# shinobi.net
KiCad netlist of a schematic drawn in EAGLE
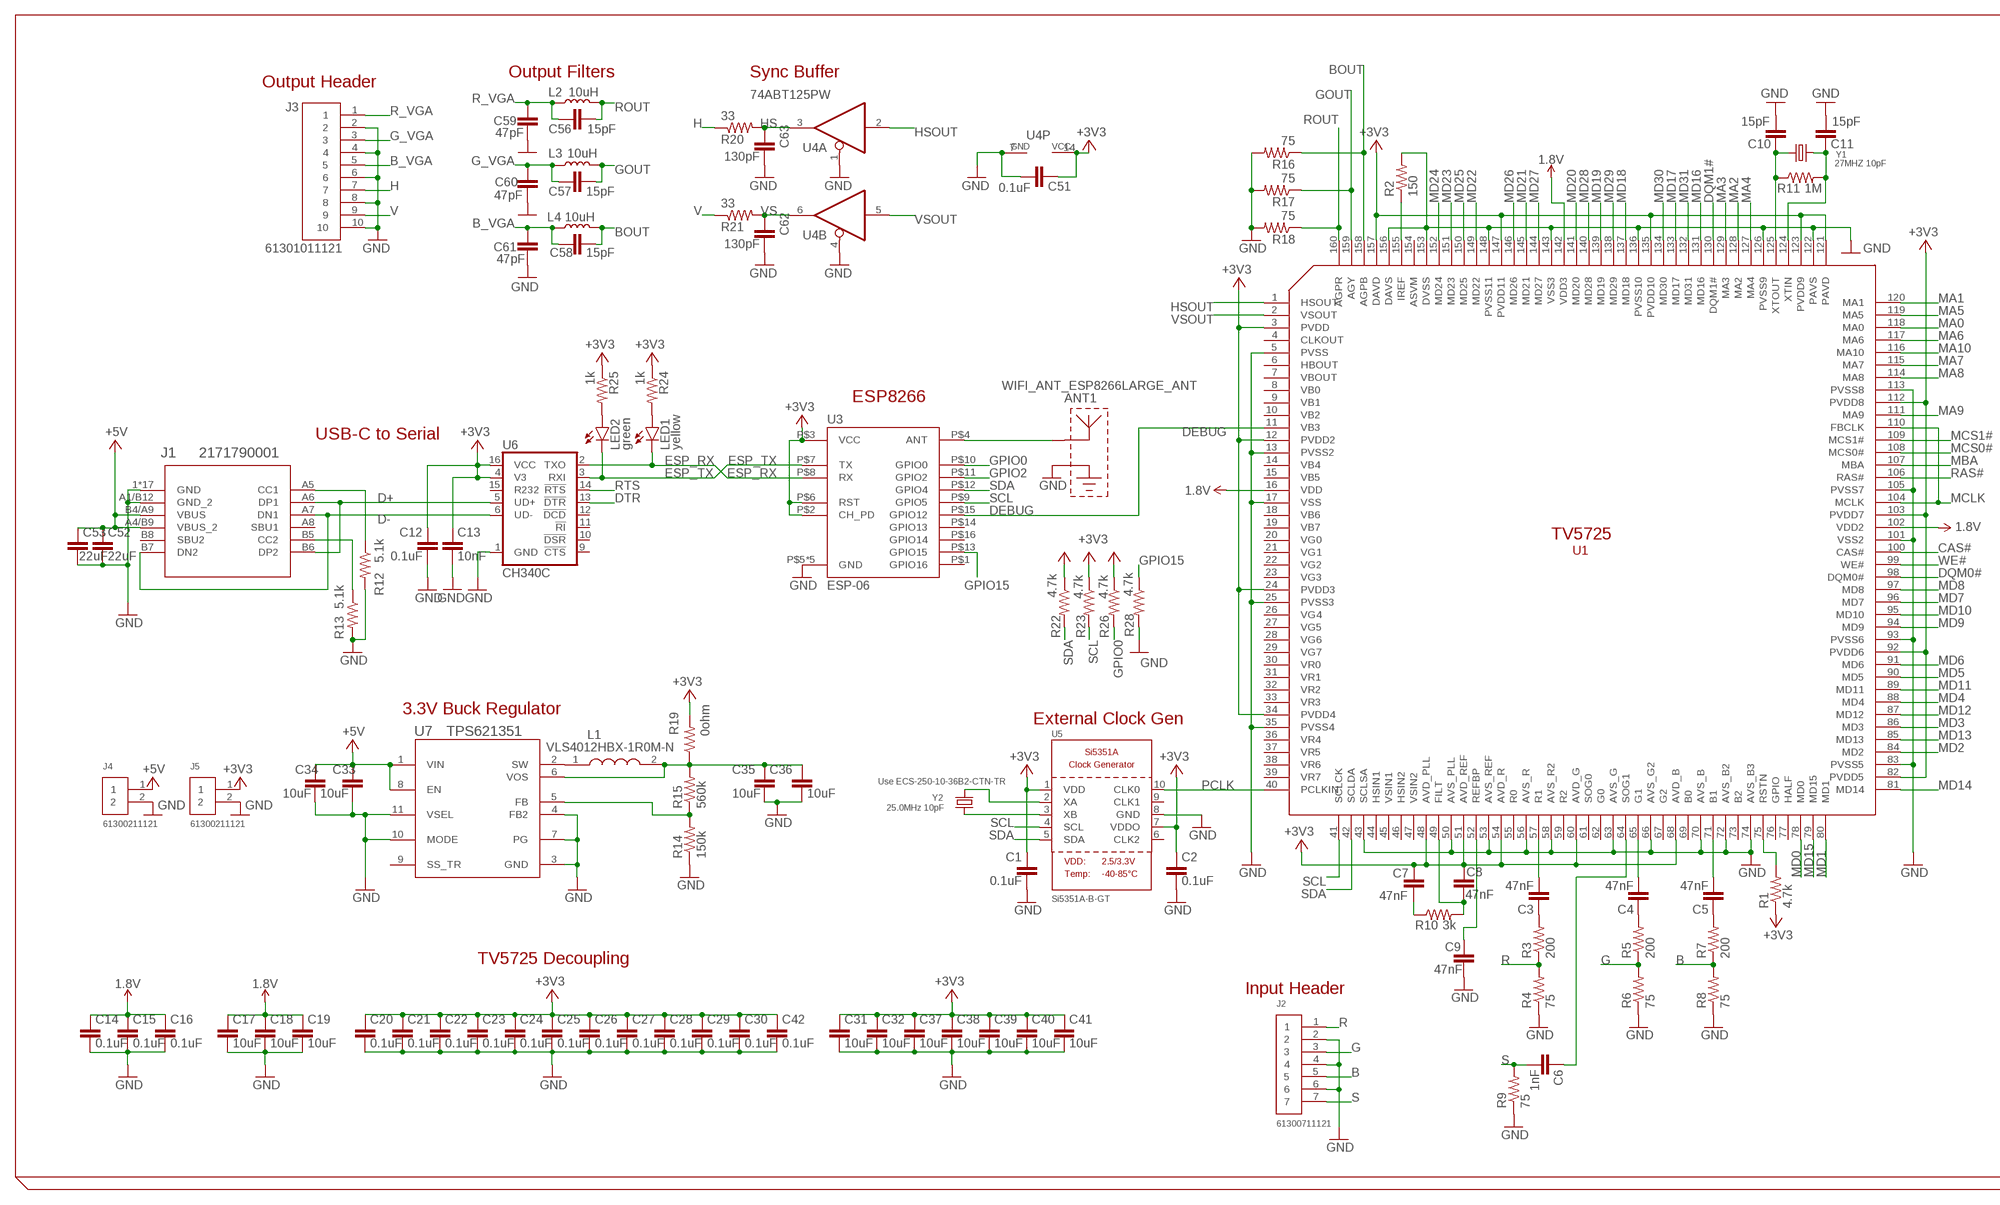
[diagram p0: schematic, sheet 1, part 1 of 2]
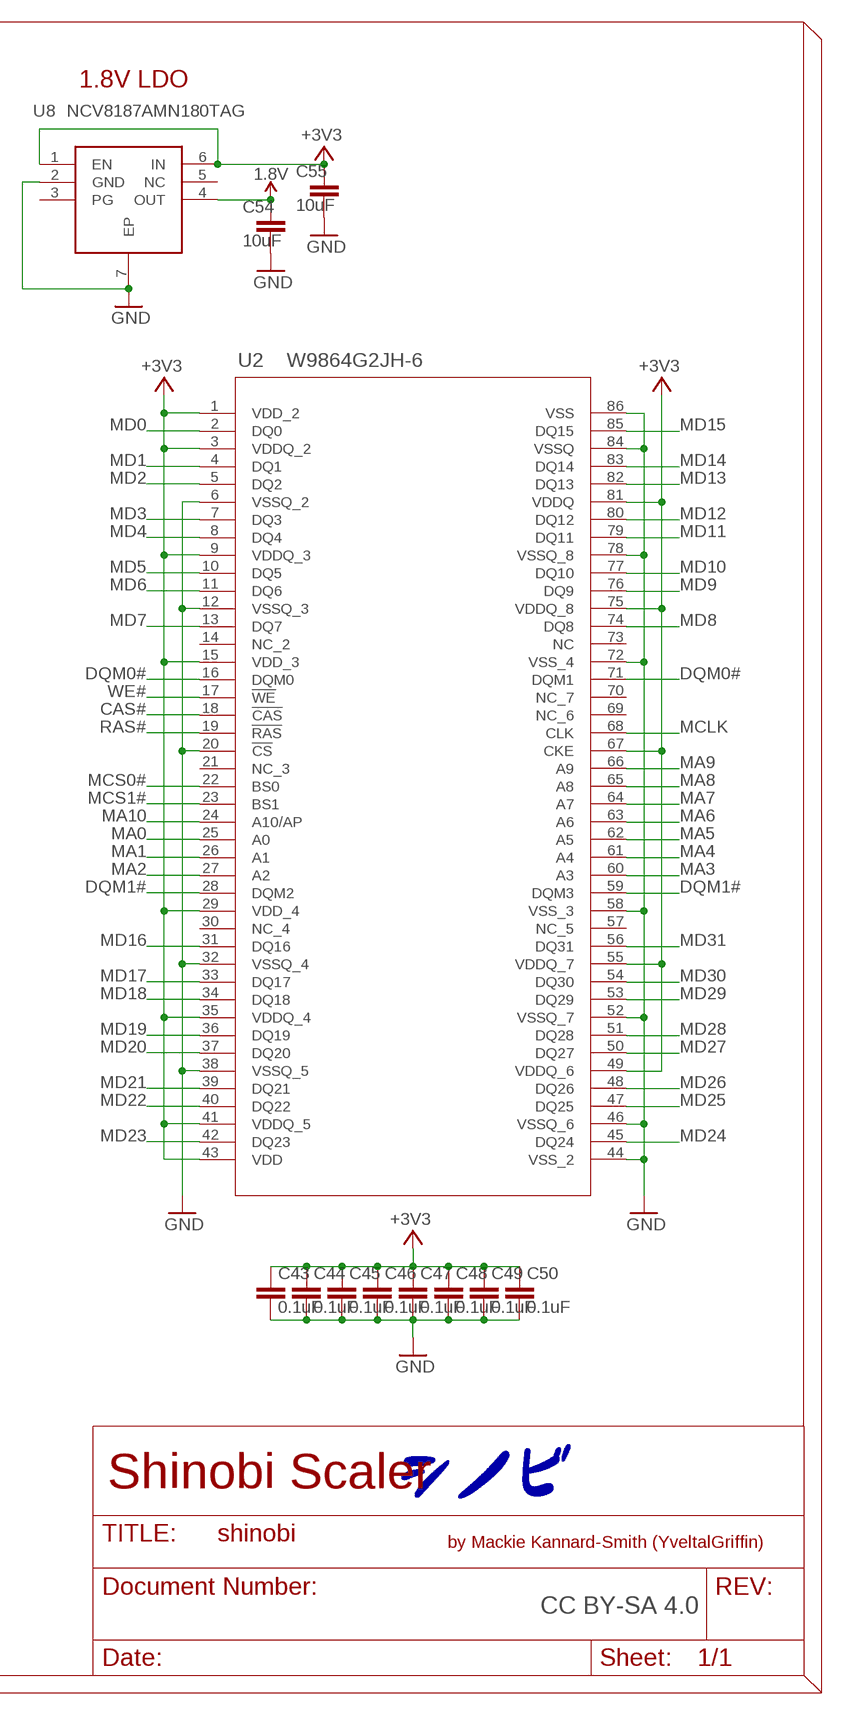
[diagram p1: schematic, sheet 1, part 2 of 2]

(export (version "E")
  (design (tool "Eeschema 10.0.6"))
  (components
    (comp (ref "ANT1")
      (value "WIFI_ANT_ESP8266LARGE_ANT")
      (footprint "eagle-import:ANTENNA")
      (libsource (lib "eagle-import") (part "WIFI_ANT_ESP8266LARGE_ANT"))
    )
    (comp (ref "C1")
      (value "0.1uF")
      (footprint "eagle-import:C0402")
      (libsource (lib "eagle-import") (part "C-USC0402"))
    )
    (comp (ref "C2")
      (value "0.1uF")
      (footprint "eagle-import:C0402")
      (libsource (lib "eagle-import") (part "C-USC0402"))
    )
    (comp (ref "C3")
      (value "47nF")
      (footprint "eagle-import:C0402")
      (libsource (lib "eagle-import") (part "C-USC0402"))
    )
    (comp (ref "C4")
      (value "47nF")
      (footprint "eagle-import:C0402")
      (libsource (lib "eagle-import") (part "C-USC0402"))
    )
    (comp (ref "C5")
      (value "47nF")
      (footprint "eagle-import:C0402")
      (libsource (lib "eagle-import") (part "C-USC0402"))
    )
    (comp (ref "C6")
      (value "1nF")
      (footprint "eagle-import:C0402")
      (libsource (lib "eagle-import") (part "C-USC0402"))
    )
    (comp (ref "C7")
      (value "47nF")
      (footprint "eagle-import:C0402")
      (libsource (lib "eagle-import") (part "C-USC0402"))
    )
    (comp (ref "C8")
      (value "47nF")
      (footprint "eagle-import:C0402")
      (libsource (lib "eagle-import") (part "C-USC0402"))
    )
    (comp (ref "C9")
      (value "47nF")
      (footprint "eagle-import:C0402")
      (libsource (lib "eagle-import") (part "C-USC0402"))
    )
    (comp (ref "C10")
      (value "15pF")
      (footprint "eagle-import:C0402")
      (libsource (lib "eagle-import") (part "C-USC0402"))
    )
    (comp (ref "C11")
      (value "15pF")
      (footprint "eagle-import:C0402")
      (libsource (lib "eagle-import") (part "C-USC0402"))
    )
    (comp (ref "C12")
      (value "0.1uF")
      (footprint "eagle-import:C0402")
      (libsource (lib "eagle-import") (part "C-USC0402"))
    )
    (comp (ref "C13")
      (value "10nF")
      (footprint "eagle-import:C0402")
      (libsource (lib "eagle-import") (part "C-USC0402"))
    )
    (comp (ref "C14")
      (value "0.1uF")
      (footprint "eagle-import:C0402")
      (libsource (lib "eagle-import") (part "C-USC0402"))
    )
    (comp (ref "C15")
      (value "0.1uF")
      (footprint "eagle-import:C0402")
      (libsource (lib "eagle-import") (part "C-USC0402"))
    )
    (comp (ref "C16")
      (value "0.1uF")
      (footprint "eagle-import:C0402")
      (libsource (lib "eagle-import") (part "C-USC0402"))
    )
    (comp (ref "C17")
      (value "10uF")
      (footprint "eagle-import:C0603")
      (libsource (lib "eagle-import") (part "C-USC0603"))
    )
    (comp (ref "C18")
      (value "10uF")
      (footprint "eagle-import:C0603")
      (libsource (lib "eagle-import") (part "C-USC0603"))
    )
    (comp (ref "C19")
      (value "10uF")
      (footprint "eagle-import:C0603")
      (libsource (lib "eagle-import") (part "C-USC0603"))
    )
    (comp (ref "C20")
      (value "0.1uF")
      (footprint "eagle-import:C0402")
      (libsource (lib "eagle-import") (part "C-USC0402"))
    )
    (comp (ref "C21")
      (value "0.1uF")
      (footprint "eagle-import:C0402")
      (libsource (lib "eagle-import") (part "C-USC0402"))
    )
    (comp (ref "C22")
      (value "0.1uF")
      (footprint "eagle-import:C0402")
      (libsource (lib "eagle-import") (part "C-USC0402"))
    )
    (comp (ref "C23")
      (value "0.1uF")
      (footprint "eagle-import:C0402")
      (libsource (lib "eagle-import") (part "C-USC0402"))
    )
    (comp (ref "C24")
      (value "0.1uF")
      (footprint "eagle-import:C0402")
      (libsource (lib "eagle-import") (part "C-USC0402"))
    )
    (comp (ref "C25")
      (value "0.1uF")
      (footprint "eagle-import:C0402")
      (libsource (lib "eagle-import") (part "C-USC0402"))
    )
    (comp (ref "C26")
      (value "0.1uF")
      (footprint "eagle-import:C0402")
      (libsource (lib "eagle-import") (part "C-USC0402"))
    )
    (comp (ref "C27")
      (value "0.1uF")
      (footprint "eagle-import:C0402")
      (libsource (lib "eagle-import") (part "C-USC0402"))
    )
    (comp (ref "C28")
      (value "0.1uF")
      (footprint "eagle-import:C0402")
      (libsource (lib "eagle-import") (part "C-USC0402"))
    )
    (comp (ref "C29")
      (value "0.1uF")
      (footprint "eagle-import:C0402")
      (libsource (lib "eagle-import") (part "C-USC0402"))
    )
    (comp (ref "C30")
      (value "0.1uF")
      (footprint "eagle-import:C0402")
      (libsource (lib "eagle-import") (part "C-USC0402"))
    )
    (comp (ref "C31")
      (value "10uF")
      (footprint "eagle-import:C0603")
      (libsource (lib "eagle-import") (part "C-USC0603"))
    )
    (comp (ref "C32")
      (value "10uF")
      (footprint "eagle-import:C0603")
      (libsource (lib "eagle-import") (part "C-USC0603"))
    )
    (comp (ref "C33")
      (value "10uF")
      (footprint "eagle-import:C0603")
      (libsource (lib "eagle-import") (part "C-USC0603"))
    )
    (comp (ref "C34")
      (value "10uF")
      (footprint "eagle-import:C0603")
      (libsource (lib "eagle-import") (part "C-USC0603"))
    )
    (comp (ref "C35")
      (value "10uF")
      (footprint "eagle-import:C0603")
      (libsource (lib "eagle-import") (part "C-USC0603"))
    )
    (comp (ref "C36")
      (value "10uF")
      (footprint "eagle-import:C0603")
      (libsource (lib "eagle-import") (part "C-USC0603"))
    )
    (comp (ref "C37")
      (value "10uF")
      (footprint "eagle-import:C0603")
      (libsource (lib "eagle-import") (part "C-USC0603"))
    )
    (comp (ref "C38")
      (value "10uF")
      (footprint "eagle-import:C0603")
      (libsource (lib "eagle-import") (part "C-USC0603"))
    )
    (comp (ref "C39")
      (value "10uF")
      (footprint "eagle-import:C0603")
      (libsource (lib "eagle-import") (part "C-USC0603"))
    )
    (comp (ref "C40")
      (value "10uF")
      (footprint "eagle-import:C0603")
      (libsource (lib "eagle-import") (part "C-USC0603"))
    )
    (comp (ref "C41")
      (value "10uF")
      (footprint "eagle-import:C0603")
      (libsource (lib "eagle-import") (part "C-USC0603"))
    )
    (comp (ref "C42")
      (value "0.1uF")
      (footprint "eagle-import:C0402")
      (libsource (lib "eagle-import") (part "C-USC0402"))
    )
    (comp (ref "C43")
      (value "0.1uF")
      (footprint "eagle-import:C0402")
      (libsource (lib "eagle-import") (part "C-USC0402"))
    )
    (comp (ref "C44")
      (value "0.1uF")
      (footprint "eagle-import:C0402")
      (libsource (lib "eagle-import") (part "C-USC0402"))
    )
    (comp (ref "C45")
      (value "0.1uF")
      (footprint "eagle-import:C0402")
      (libsource (lib "eagle-import") (part "C-USC0402"))
    )
    (comp (ref "C46")
      (value "0.1uF")
      (footprint "eagle-import:C0402")
      (libsource (lib "eagle-import") (part "C-USC0402"))
    )
    (comp (ref "C47")
      (value "0.1uF")
      (footprint "eagle-import:C0402")
      (libsource (lib "eagle-import") (part "C-USC0402"))
    )
    (comp (ref "C48")
      (value "0.1uF")
      (footprint "eagle-import:C0402")
      (libsource (lib "eagle-import") (part "C-USC0402"))
    )
    (comp (ref "C49")
      (value "0.1uF")
      (footprint "eagle-import:C0402")
      (libsource (lib "eagle-import") (part "C-USC0402"))
    )
    (comp (ref "C50")
      (value "0.1uF")
      (footprint "eagle-import:C0402")
      (libsource (lib "eagle-import") (part "C-USC0402"))
    )
    (comp (ref "C51")
      (value "0.1uF")
      (footprint "eagle-import:C0402")
      (libsource (lib "eagle-import") (part "C-USC0402"))
    )
    (comp (ref "C52")
      (value "22uF")
      (footprint "eagle-import:C0805")
      (libsource (lib "eagle-import") (part "C-USC0805"))
    )
    (comp (ref "C53")
      (value "22uF")
      (footprint "eagle-import:C0805")
      (libsource (lib "eagle-import") (part "C-USC0805"))
    )
    (comp (ref "C54")
      (value "10uF")
      (footprint "eagle-import:C0603")
      (libsource (lib "eagle-import") (part "C-USC0603"))
    )
    (comp (ref "C55")
      (value "10uF")
      (footprint "eagle-import:C0603")
      (libsource (lib "eagle-import") (part "C-USC0603"))
    )
    (comp (ref "C56")
      (value "15pF")
      (footprint "eagle-import:C0402")
      (libsource (lib "eagle-import") (part "C-USC0402"))
    )
    (comp (ref "C57")
      (value "15pF")
      (footprint "eagle-import:C0402")
      (libsource (lib "eagle-import") (part "C-USC0402"))
    )
    (comp (ref "C58")
      (value "15pF")
      (footprint "eagle-import:C0402")
      (libsource (lib "eagle-import") (part "C-USC0402"))
    )
    (comp (ref "C59")
      (value "47pF")
      (footprint "eagle-import:C0402")
      (libsource (lib "eagle-import") (part "C-USC0402"))
    )
    (comp (ref "C60")
      (value "47pF")
      (footprint "eagle-import:C0402")
      (libsource (lib "eagle-import") (part "C-USC0402"))
    )
    (comp (ref "C61")
      (value "47pF")
      (footprint "eagle-import:C0402")
      (libsource (lib "eagle-import") (part "C-USC0402"))
    )
    (comp (ref "C62")
      (value "130pF")
      (footprint "eagle-import:C0402")
      (libsource (lib "eagle-import") (part "C-USC0402"))
    )
    (comp (ref "C63")
      (value "130pF")
      (footprint "eagle-import:C0402")
      (libsource (lib "eagle-import") (part "C-USC0402"))
    )
    (comp (ref "J1")
      (value "2171790001")
      (footprint "eagle-import:2171790001_MOL")
      (fields (field (name "COPYRIGHT") "Copyright (C) 2022 Ultra Librarian. All rights reserved."))
      (libsource (lib "eagle-import") (part "2171790001"))
    )
    (comp (ref "J2")
      (value "61300711121")
      (footprint "eagle-import:61300711121")
      (fields
        (field (name "DIGI_KEY_PART_NUMBER") "732-5320-ND")
        (field (name "MANUFACTURER") "Wurth Electronics Inc.")
        (field (name "CREATED_BY") "PCBLayout.com")
      )
      (libsource (lib "eagle-import") (part "61300711121"))
    )
    (comp (ref "J3")
      (value "61301011121")
      (footprint "eagle-import:61301011121")
      (fields
        (field (name "DIGIKEY_PART_NUMBER") "732-2670-ND")
        (field (name "MANUFACTURER") "Wurth Electronics Inc.")
        (field (name "CREATED_BY") "PCBLayout.com")
      )
      (libsource (lib "eagle-import") (part "61301011121"))
    )
    (comp (ref "J4")
      (value "61300211121")
      (footprint "eagle-import:61300211121")
      (fields
        (field (name "DIGI_KEY_PART_NUMBER") "732-5315-ND")
        (field (name "MANUFACTURER") "Wurth Electronics Inc.")
        (field (name "CREATED_BY") "PCBLayout.com")
      )
      (libsource (lib "eagle-import") (part "61300211121"))
    )
    (comp (ref "J5")
      (value "61300211121")
      (footprint "eagle-import:61300211121")
      (fields
        (field (name "DIGI_KEY_PART_NUMBER") "732-5315-ND")
        (field (name "MANUFACTURER") "Wurth Electronics Inc.")
        (field (name "CREATED_BY") "PCBLayout.com")
      )
      (libsource (lib "eagle-import") (part "61300211121"))
    )
    (comp (ref "L1")
      (value "VLS4012HBX-1R0M-N")
      (footprint "eagle-import:VLS4012")
      (fields (field (name "MOUSER_PART_NUMBER") "810-VLS4012HBX1R0M-N"))
      (libsource (lib "eagle-import") (part "VLS4012HBX-1R0M-N"))
    )
    (comp (ref "L2")
      (value "10uH")
      (footprint "eagle-import:R0402")
      (libsource (lib "eagle-import") (part "L0402"))
    )
    (comp (ref "L3")
      (value "10uH")
      (footprint "eagle-import:R0402")
      (libsource (lib "eagle-import") (part "L0402"))
    )
    (comp (ref "L4")
      (value "10uH")
      (footprint "eagle-import:R0402")
      (libsource (lib "eagle-import") (part "L0402"))
    )
    (comp (ref "LED1")
      (value "yellow")
      (footprint "eagle-import:CHIP-LED0603")
      (libsource (lib "eagle-import") (part "LEDCHIP-LED0603"))
    )
    (comp (ref "LED2")
      (value "green")
      (footprint "eagle-import:CHIP-LED0603")
      (libsource (lib "eagle-import") (part "LEDCHIP-LED0603"))
    )
    (comp (ref "R1")
      (value "4.7k")
      (footprint "eagle-import:R0402")
      (libsource (lib "eagle-import") (part "R-US_R0402"))
    )
    (comp (ref "R2")
      (value "150")
      (footprint "eagle-import:R0402")
      (libsource (lib "eagle-import") (part "R-US_R0402"))
    )
    (comp (ref "R3")
      (value "200")
      (footprint "eagle-import:R0402")
      (libsource (lib "eagle-import") (part "R-US_R0402"))
    )
    (comp (ref "R4")
      (value "75")
      (footprint "eagle-import:R0402")
      (libsource (lib "eagle-import") (part "R-US_R0402"))
    )
    (comp (ref "R5")
      (value "200")
      (footprint "eagle-import:R0402")
      (libsource (lib "eagle-import") (part "R-US_R0402"))
    )
    (comp (ref "R6")
      (value "75")
      (footprint "eagle-import:R0402")
      (libsource (lib "eagle-import") (part "R-US_R0402"))
    )
    (comp (ref "R7")
      (value "200")
      (footprint "eagle-import:R0402")
      (libsource (lib "eagle-import") (part "R-US_R0402"))
    )
    (comp (ref "R8")
      (value "75")
      (footprint "eagle-import:R0402")
      (libsource (lib "eagle-import") (part "R-US_R0402"))
    )
    (comp (ref "R9")
      (value "75")
      (footprint "eagle-import:R0402")
      (libsource (lib "eagle-import") (part "R-US_R0402"))
    )
    (comp (ref "R10")
      (value "3k")
      (footprint "eagle-import:R0402")
      (libsource (lib "eagle-import") (part "R-US_R0402"))
    )
    (comp (ref "R11")
      (value "1M")
      (footprint "eagle-import:R0402")
      (libsource (lib "eagle-import") (part "R-US_R0402"))
    )
    (comp (ref "R12")
      (value "5.1k")
      (footprint "eagle-import:R0402")
      (libsource (lib "eagle-import") (part "R-US_R0402"))
    )
    (comp (ref "R13")
      (value "5.1k")
      (footprint "eagle-import:R0402")
      (libsource (lib "eagle-import") (part "R-US_R0402"))
    )
    (comp (ref "R14")
      (value "150k")
      (footprint "eagle-import:R0402")
      (libsource (lib "eagle-import") (part "R-US_R0402"))
    )
    (comp (ref "R15")
      (value "560k")
      (footprint "eagle-import:R0402")
      (libsource (lib "eagle-import") (part "R-US_R0402"))
    )
    (comp (ref "R16")
      (value "75")
      (footprint "eagle-import:R0402")
      (libsource (lib "eagle-import") (part "R-US_R0402"))
    )
    (comp (ref "R17")
      (value "75")
      (footprint "eagle-import:R0402")
      (libsource (lib "eagle-import") (part "R-US_R0402"))
    )
    (comp (ref "R18")
      (value "75")
      (footprint "eagle-import:R0402")
      (libsource (lib "eagle-import") (part "R-US_R0402"))
    )
    (comp (ref "R19")
      (value "0ohm")
      (footprint "eagle-import:R0805")
      (libsource (lib "eagle-import") (part "R-US_R0805"))
    )
    (comp (ref "R20")
      (value "33")
      (footprint "eagle-import:R0402")
      (libsource (lib "eagle-import") (part "R-US_R0402"))
    )
    (comp (ref "R21")
      (value "33")
      (footprint "eagle-import:R0402")
      (libsource (lib "eagle-import") (part "R-US_R0402"))
    )
    (comp (ref "R22")
      (value "4.7k")
      (footprint "eagle-import:R0402")
      (libsource (lib "eagle-import") (part "R-US_R0402"))
    )
    (comp (ref "R23")
      (value "4.7k")
      (footprint "eagle-import:R0402")
      (libsource (lib "eagle-import") (part "R-US_R0402"))
    )
    (comp (ref "R24")
      (value "1k")
      (footprint "eagle-import:R0402")
      (libsource (lib "eagle-import") (part "R-US_R0402"))
    )
    (comp (ref "R25")
      (value "1k")
      (footprint "eagle-import:R0402")
      (libsource (lib "eagle-import") (part "R-US_R0402"))
    )
    (comp (ref "R26")
      (value "4.7k")
      (footprint "eagle-import:R0402")
      (libsource (lib "eagle-import") (part "R-US_R0402"))
    )
    (comp (ref "R28")
      (value "4.7k")
      (footprint "eagle-import:R0402")
      (libsource (lib "eagle-import") (part "R-US_R0402"))
    )
    (comp (ref "U1")
      (value "TV5725")
      (footprint "eagle-import:PQFP160")
      (libsource (lib "eagle-import") (part "TV5725"))
    )
    (comp (ref "U2")
      (value "W9864G2JH-6")
      (footprint "eagle-import:WIN_TSOP-86_WIN")
      (fields (field (name "COPYRIGHT") "Copyright (C) 2022 Ultra Librarian. All rights reserved."))
      (libsource (lib "eagle-import") (part "W9864G2JH-6"))
    )
    (comp (ref "U3")
      (value "ESP-06")
      (footprint "eagle-import:ESP-06")
      (libsource (lib "eagle-import") (part "ESP-06"))
    )
    (comp (ref "U4")
      (value "74ABT125PW")
      (footprint "eagle-import:TSSOP14")
      (libsource (lib "eagle-import") (part "74125PWABT"))
    )
    (comp (ref "U5")
      (value "Si5351A-B-GT")
      (footprint "eagle-import:MSOP10")
      (libsource (lib "eagle-import") (part "SI5351A"))
    )
    (comp (ref "U6")
      (value "CH340C")
      (footprint "eagle-import:SO016")
      (libsource (lib "eagle-import") (part "CH340C"))
    )
    (comp (ref "U7")
      (value "TPS621351")
      (footprint "eagle-import:RGX0011A")
      (fields
        (field (name "MANUFACTURER") "Texas Instruments")
        (field (name "MANUFACTURER_PART_NUMBER") "TPS621351RGXR")
      )
      (libsource (lib "eagle-import") (part "TPS621351RGXR"))
    )
    (comp (ref "U8")
      (value "NCV8187AMN180TAG")
      (footprint "eagle-import:SON95P300X300X95-7N")
      (fields (field (name "MOUSER_PART_NUMBER") "863-NCV8187AMN180TAG"))
      (libsource (lib "eagle-import") (part "NCV8187AMN180TAG"))
    )
    (comp (ref "Y1")
      (value "27MHZ 10pF")
      (footprint "eagle-import:CRYSTAL_2.5X2")
      (libsource (lib "eagle-import") (part "CRYSTAL2.5X2.0"))
    )
    (comp (ref "Y2")
      (value "25.0MHz 10pF")
      (footprint "eagle-import:CRYSTAL_2.5X2")
      (libsource (lib "eagle-import") (part "CRYSTAL2.5X2.0"))
    )
  )
  (nets
    (net (code "1") (name "+3V3") (class "Default")
      (node (ref "C1") (pin "1") (pinfunction "1_1") (pintype "passive"))
      (node (ref "C12") (pin "1") (pinfunction "1_1") (pintype "passive"))
      (node (ref "C13") (pin "1") (pinfunction "1_1") (pintype "passive"))
      (node (ref "C2") (pin "1") (pinfunction "1_1") (pintype "passive"))
      (node (ref "C20") (pin "1") (pinfunction "1_1") (pintype "passive"))
      (node (ref "C21") (pin "1") (pinfunction "1_1") (pintype "passive"))
      (node (ref "C22") (pin "1") (pinfunction "1_1") (pintype "passive"))
      (node (ref "C23") (pin "1") (pinfunction "1_1") (pintype "passive"))
      (node (ref "C24") (pin "1") (pinfunction "1_1") (pintype "passive"))
      (node (ref "C25") (pin "1") (pinfunction "1_1") (pintype "passive"))
      (node (ref "C26") (pin "1") (pinfunction "1_1") (pintype "passive"))
      (node (ref "C27") (pin "1") (pinfunction "1_1") (pintype "passive"))
      (node (ref "C28") (pin "1") (pinfunction "1_1") (pintype "passive"))
      (node (ref "C29") (pin "1") (pinfunction "1_1") (pintype "passive"))
      (node (ref "C30") (pin "1") (pinfunction "1_1") (pintype "passive"))
      (node (ref "C31") (pin "1") (pinfunction "1_1") (pintype "passive"))
      (node (ref "C32") (pin "1") (pinfunction "1_1") (pintype "passive"))
      (node (ref "C37") (pin "1") (pinfunction "1_1") (pintype "passive"))
      (node (ref "C38") (pin "1") (pinfunction "1_1") (pintype "passive"))
      (node (ref "C39") (pin "1") (pinfunction "1_1") (pintype "passive"))
      (node (ref "C40") (pin "1") (pinfunction "1_1") (pintype "passive"))
      (node (ref "C41") (pin "1") (pinfunction "1_1") (pintype "passive"))
      (node (ref "C42") (pin "1") (pinfunction "1_1") (pintype "passive"))
      (node (ref "C43") (pin "1") (pinfunction "1_1") (pintype "passive"))
      (node (ref "C44") (pin "1") (pinfunction "1_1") (pintype "passive"))
      (node (ref "C45") (pin "1") (pinfunction "1_1") (pintype "passive"))
      (node (ref "C46") (pin "1") (pinfunction "1_1") (pintype "passive"))
      (node (ref "C47") (pin "1") (pinfunction "1_1") (pintype "passive"))
      (node (ref "C48") (pin "1") (pinfunction "1_1") (pintype "passive"))
      (node (ref "C49") (pin "1") (pinfunction "1_1") (pintype "passive"))
      (node (ref "C50") (pin "1") (pinfunction "1_1") (pintype "passive"))
      (node (ref "C51") (pin "1") (pinfunction "1_1") (pintype "passive"))
      (node (ref "C55") (pin "1") (pinfunction "1_1") (pintype "passive"))
      (node (ref "C7") (pin "2") (pinfunction "2_2") (pintype "passive"))
      (node (ref "C8") (pin "2") (pinfunction "2_2") (pintype "passive"))
      (node (ref "J5") (pin "1") (pinfunction "1_1") (pintype "passive"))
      (node (ref "R1") (pin "1") (pinfunction "1_1") (pintype "passive"))
      (node (ref "R19") (pin "2") (pinfunction "2_2") (pintype "passive"))
      (node (ref "R22") (pin "1") (pinfunction "1_1") (pintype "passive"))
      (node (ref "R23") (pin "1") (pinfunction "1_1") (pintype "passive"))
      (node (ref "R24") (pin "1") (pinfunction "1_1") (pintype "passive"))
      (node (ref "R25") (pin "1") (pinfunction "1_1") (pintype "passive"))
      (node (ref "R26") (pin "1") (pinfunction "1_1") (pintype "passive"))
      (node (ref "U1") (pin "103") (pinfunction "PVDD7_103") (pintype "bidirectional"))
      (node (ref "U1") (pin "112") (pinfunction "PVDD8_112") (pintype "bidirectional"))
      (node (ref "U1") (pin "12") (pinfunction "PVDD2_12") (pintype "bidirectional"))
      (node (ref "U1") (pin "121") (pinfunction "PAVD_121") (pintype "bidirectional"))
      (node (ref "U1") (pin "123") (pinfunction "PVDD9_123") (pintype "bidirectional"))
      (node (ref "U1") (pin "135") (pinfunction "PVDD10_135") (pintype "bidirectional"))
      (node (ref "U1") (pin "147") (pinfunction "PVDD11_147") (pintype "bidirectional"))
      (node (ref "U1") (pin "157") (pinfunction "DAVD_157") (pintype "bidirectional"))
      (node (ref "U1") (pin "24") (pinfunction "PVDD3_24") (pintype "bidirectional"))
      (node (ref "U1") (pin "3") (pinfunction "PVDD_3") (pintype "bidirectional"))
      (node (ref "U1") (pin "34") (pinfunction "PVDD4_34") (pintype "bidirectional"))
      (node (ref "U1") (pin "48") (pinfunction "AVD_PLL_48") (pintype "bidirectional"))
      (node (ref "U1") (pin "51") (pinfunction "AVD_REF_51") (pintype "bidirectional"))
      (node (ref "U1") (pin "54") (pinfunction "AVD_R_54") (pintype "bidirectional"))
      (node (ref "U1") (pin "60") (pinfunction "AVD_G_60") (pintype "bidirectional"))
      (node (ref "U1") (pin "68") (pinfunction "AVD_B_68") (pintype "bidirectional"))
      (node (ref "U1") (pin "82") (pinfunction "PVDD5_82") (pintype "bidirectional"))
      (node (ref "U1") (pin "92") (pinfunction "PVDD6_92") (pintype "bidirectional"))
      (node (ref "U2") (pin "1") (pinfunction "VDD_2_1") (pintype "power_in"))
      (node (ref "U2") (pin "15") (pinfunction "VDD_3_15") (pintype "power_in"))
      (node (ref "U2") (pin "29") (pinfunction "VDD_4_29") (pintype "power_in"))
      (node (ref "U2") (pin "3") (pinfunction "VDDQ_2_3") (pintype "power_in"))
      (node (ref "U2") (pin "35") (pinfunction "VDDQ_4_35") (pintype "power_in"))
      (node (ref "U2") (pin "41") (pinfunction "VDDQ_5_41") (pintype "power_in"))
      (node (ref "U2") (pin "43") (pinfunction "VDD_43") (pintype "power_in"))
      (node (ref "U2") (pin "49") (pinfunction "VDDQ_6_49") (pintype "power_in"))
      (node (ref "U2") (pin "55") (pinfunction "VDDQ_7_55") (pintype "power_in"))
      (node (ref "U2") (pin "67") (pinfunction "CKE_67") (pintype "passive"))
      (node (ref "U2") (pin "75") (pinfunction "VDDQ_8_75") (pintype "power_in"))
      (node (ref "U2") (pin "81") (pinfunction "VDDQ_81") (pintype "power_in"))
      (node (ref "U2") (pin "9") (pinfunction "VDDQ_3_9") (pintype "power_in"))
      (node (ref "U3") (pin "P$2") (pinfunction "CH_PD_P$2") (pintype "bidirectional"))
      (node (ref "U3") (pin "P$3") (pinfunction "VCC_P$3") (pintype "bidirectional"))
      (node (ref "U3") (pin "P$6") (pinfunction "RST_P$6") (pintype "bidirectional"))
      (node (ref "U4") (pin "14") (pinfunction "VCC_14") (pintype "power_in"))
      (node (ref "U5") (pin "1") (pinfunction "VDD_1") (pintype "power_in"))
      (node (ref "U5") (pin "7") (pinfunction "VDDO_7") (pintype "power_in"))
      (node (ref "U6") (pin "16") (pinfunction "VCC_16") (pintype "bidirectional"))
      (node (ref "U6") (pin "4") (pinfunction "V3_4") (pintype "bidirectional"))
      (node (ref "U8") (pin "1") (pinfunction "EN_1") (pintype "bidirectional"))
      (node (ref "U8") (pin "6") (pinfunction "IN_6") (pintype "bidirectional"))
    )
    (net (code "2") (name "+5V") (class "Default")
      (node (ref "C33") (pin "1") (pinfunction "1_1") (pintype "passive"))
      (node (ref "C34") (pin "1") (pinfunction "1_1") (pintype "passive"))
      (node (ref "C52") (pin "1") (pinfunction "1_1") (pintype "passive"))
      (node (ref "C53") (pin "1") (pinfunction "1_1") (pintype "passive"))
      (node (ref "J1") (pin "A4/B9") (pinfunction "VBUS_2_A4/B9") (pintype "power_in"))
      (node (ref "J1") (pin "B4/A9") (pinfunction "VBUS_B4/A9") (pintype "power_in"))
      (node (ref "J4") (pin "1") (pinfunction "1_1") (pintype "passive"))
      (node (ref "U7") (pin "1") (pinfunction "VIN_1") (pintype "power_in"))
      (node (ref "U7") (pin "8") (pinfunction "EN_8") (pintype "input"))
    )
    (net (code "3") (name "/B") (class "Default")
      (node (ref "J2") (pin "5") (pinfunction "5_5") (pintype "passive"))
      (node (ref "R7") (pin "1") (pinfunction "1_1") (pintype "passive"))
      (node (ref "R8") (pin "2") (pinfunction "2_2") (pintype "passive"))
    )
    (net (code "4") (name "/BOUT") (class "Default")
      (node (ref "C58") (pin "1") (pinfunction "1_1") (pintype "passive"))
      (node (ref "L4") (pin "1") (pinfunction "P$1_1") (pintype "bidirectional"))
      (node (ref "R16") (pin "1") (pinfunction "1_1") (pintype "passive"))
      (node (ref "U1") (pin "158") (pinfunction "AGPB_158") (pintype "bidirectional"))
    )
    (net (code "5") (name "/B_VGA") (class "Default")
      (node (ref "C58") (pin "2") (pinfunction "2_2") (pintype "passive"))
      (node (ref "C61") (pin "1") (pinfunction "1_1") (pintype "passive"))
      (node (ref "J3") (pin "5") (pinfunction "5_5") (pintype "passive"))
      (node (ref "L4") (pin "2") (pinfunction "P$2_2") (pintype "bidirectional"))
    )
    (net (code "6") (name "/CAS#") (class "Default")
      (node (ref "U1") (pin "100") (pinfunction "CAS#_100") (pintype "bidirectional"))
      (node (ref "U2") (pin "18") (pinfunction "~{CAS}_18") (pintype "passive"))
    )
    (net (code "7") (name "/D+") (class "Default")
      (node (ref "J1") (pin "A6") (pinfunction "DP1_A6") (pintype "bidirectional"))
      (node (ref "J1") (pin "B6") (pinfunction "DP2_B6") (pintype "bidirectional"))
      (node (ref "U6") (pin "5") (pinfunction "UD+_5") (pintype "bidirectional"))
    )
    (net (code "8") (name "/D-") (class "Default")
      (node (ref "J1") (pin "A7") (pinfunction "DN1_A7") (pintype "bidirectional"))
      (node (ref "J1") (pin "B7") (pinfunction "DN2_B7") (pintype "bidirectional"))
      (node (ref "U6") (pin "6") (pinfunction "UD-_6") (pintype "bidirectional"))
    )
    (net (code "9") (name "/DEBUG") (class "Default")
      (node (ref "U1") (pin "11") (pinfunction "VB3_11") (pintype "bidirectional"))
      (node (ref "U3") (pin "P$15") (pinfunction "GPIO12_P$15") (pintype "bidirectional"))
    )
    (net (code "10") (name "/DQM0#") (class "Default")
      (node (ref "U1") (pin "98") (pinfunction "DQM0#_98") (pintype "bidirectional"))
      (node (ref "U2") (pin "16") (pinfunction "DQM0_16") (pintype "bidirectional"))
      (node (ref "U2") (pin "71") (pinfunction "DQM1_71") (pintype "bidirectional"))
    )
    (net (code "11") (name "/DQM1#") (class "Default")
      (node (ref "U1") (pin "130") (pinfunction "DQM1#_130") (pintype "bidirectional"))
      (node (ref "U2") (pin "28") (pinfunction "DQM2_28") (pintype "bidirectional"))
      (node (ref "U2") (pin "59") (pinfunction "DQM3_59") (pintype "bidirectional"))
    )
    (net (code "12") (name "/DTR") (class "Default")
      (node (ref "U6") (pin "13") (pinfunction "~{DTR}_13") (pintype "bidirectional"))
    )
    (net (code "13") (name "/ESP_RX") (class "Default")
      (node (ref "LED1") (pin "C") (pinfunction "C_C") (pintype "passive"))
      (node (ref "U3") (pin "P$8") (pinfunction "RX_P$8") (pintype "bidirectional"))
      (node (ref "U6") (pin "2") (pinfunction "TXO_2") (pintype "bidirectional"))
    )
    (net (code "14") (name "/ESP_TX") (class "Default")
      (node (ref "LED2") (pin "C") (pinfunction "C_C") (pintype "passive"))
      (node (ref "U3") (pin "P$7") (pinfunction "TX_P$7") (pintype "bidirectional"))
      (node (ref "U6") (pin "3") (pinfunction "RXI_3") (pintype "bidirectional"))
    )
    (net (code "15") (name "/G") (class "Default")
      (node (ref "J2") (pin "3") (pinfunction "3_3") (pintype "passive"))
      (node (ref "R5") (pin "1") (pinfunction "1_1") (pintype "passive"))
      (node (ref "R6") (pin "2") (pinfunction "2_2") (pintype "passive"))
    )
    (net (code "16") (name "/GOUT") (class "Default")
      (node (ref "C57") (pin "1") (pinfunction "1_1") (pintype "passive"))
      (node (ref "L3") (pin "1") (pinfunction "P$1_1") (pintype "bidirectional"))
      (node (ref "R17") (pin "1") (pinfunction "1_1") (pintype "passive"))
      (node (ref "U1") (pin "159") (pinfunction "AGY_159") (pintype "bidirectional"))
    )
    (net (code "17") (name "/GPIO0") (class "Default")
      (node (ref "R26") (pin "2") (pinfunction "2_2") (pintype "passive"))
      (node (ref "U3") (pin "P$10") (pinfunction "GPIO0_P$10") (pintype "bidirectional"))
    )
    (net (code "18") (name "/GPIO2") (class "Default")
      (node (ref "U3") (pin "P$11") (pinfunction "GPIO2_P$11") (pintype "bidirectional"))
    )
    (net (code "19") (name "/GPIO15") (class "Default")
      (node (ref "R28") (pin "1") (pinfunction "1_1") (pintype "passive"))
      (node (ref "U3") (pin "P$13") (pinfunction "GPIO15_P$13") (pintype "bidirectional"))
    )
    (net (code "20") (name "/G_VGA") (class "Default")
      (node (ref "C57") (pin "2") (pinfunction "2_2") (pintype "passive"))
      (node (ref "C60") (pin "1") (pinfunction "1_1") (pintype "passive"))
      (node (ref "J3") (pin "3") (pinfunction "3_3") (pintype "passive"))
      (node (ref "L3") (pin "2") (pinfunction "P$2_2") (pintype "bidirectional"))
    )
    (net (code "21") (name "/H") (class "Default")
      (node (ref "J3") (pin "7") (pinfunction "7_7") (pintype "passive"))
      (node (ref "R20") (pin "1") (pinfunction "1_1") (pintype "passive"))
    )
    (net (code "22") (name "/HS") (class "Default")
      (node (ref "C63") (pin "1") (pinfunction "1_1") (pintype "passive"))
      (node (ref "R20") (pin "2") (pinfunction "2_2") (pintype "passive"))
      (node (ref "U4") (pin "3") (pinfunction "O_3") (pintype "tri_state"))
    )
    (net (code "23") (name "/HSOUT") (class "Default")
      (node (ref "U1") (pin "1") (pinfunction "HSOUT_1") (pintype "bidirectional"))
      (node (ref "U4") (pin "2") (pinfunction "I_2") (pintype "input"))
    )
    (net (code "24") (name "/MA0") (class "Default")
      (node (ref "U1") (pin "118") (pinfunction "MA0_118") (pintype "bidirectional"))
      (node (ref "U2") (pin "25") (pinfunction "A0_25") (pintype "input"))
    )
    (net (code "25") (name "/MA1") (class "Default")
      (node (ref "U1") (pin "120") (pinfunction "MA1_120") (pintype "bidirectional"))
      (node (ref "U2") (pin "26") (pinfunction "A1_26") (pintype "input"))
    )
    (net (code "26") (name "/MA2") (class "Default")
      (node (ref "U1") (pin "128") (pinfunction "MA2_128") (pintype "bidirectional"))
      (node (ref "U2") (pin "27") (pinfunction "A2_27") (pintype "input"))
    )
    (net (code "27") (name "/MA3") (class "Default")
      (node (ref "U1") (pin "129") (pinfunction "MA3_129") (pintype "bidirectional"))
      (node (ref "U2") (pin "60") (pinfunction "A3_60") (pintype "input"))
    )
    (net (code "28") (name "/MA4") (class "Default")
      (node (ref "U1") (pin "127") (pinfunction "MA4_127") (pintype "bidirectional"))
      (node (ref "U2") (pin "61") (pinfunction "A4_61") (pintype "input"))
    )
    (net (code "29") (name "/MA5") (class "Default")
      (node (ref "U1") (pin "119") (pinfunction "MA5_119") (pintype "bidirectional"))
      (node (ref "U2") (pin "62") (pinfunction "A5_62") (pintype "input"))
    )
    (net (code "30") (name "/MA6") (class "Default")
      (node (ref "U1") (pin "117") (pinfunction "MA6_117") (pintype "bidirectional"))
      (node (ref "U2") (pin "63") (pinfunction "A6_63") (pintype "input"))
    )
    (net (code "31") (name "/MA7") (class "Default")
      (node (ref "U1") (pin "115") (pinfunction "MA7_115") (pintype "bidirectional"))
      (node (ref "U2") (pin "64") (pinfunction "A7_64") (pintype "input"))
    )
    (net (code "32") (name "/MA8") (class "Default")
      (node (ref "U1") (pin "114") (pinfunction "MA8_114") (pintype "bidirectional"))
      (node (ref "U2") (pin "65") (pinfunction "A8_65") (pintype "input"))
    )
    (net (code "33") (name "/MA9") (class "Default")
      (node (ref "U1") (pin "111") (pinfunction "MA9_111") (pintype "bidirectional"))
      (node (ref "U2") (pin "66") (pinfunction "A9_66") (pintype "input"))
    )
    (net (code "34") (name "/MA10") (class "Default")
      (node (ref "U1") (pin "116") (pinfunction "MA10_116") (pintype "bidirectional"))
      (node (ref "U2") (pin "24") (pinfunction "A10/AP_24") (pintype "input"))
    )
    (net (code "35") (name "/MBA") (class "Default")
      (node (ref "U1") (pin "107") (pinfunction "MBA_107") (pintype "bidirectional"))
    )
    (net (code "36") (name "/MCLK") (class "Default")
      (node (ref "U1") (pin "104") (pinfunction "MCLK_104") (pintype "bidirectional"))
      (node (ref "U1") (pin "110") (pinfunction "FBCLK_110") (pintype "bidirectional"))
      (node (ref "U2") (pin "68") (pinfunction "CLK_68") (pintype "input"))
    )
    (net (code "37") (name "/MCS0#") (class "Default")
      (node (ref "U1") (pin "108") (pinfunction "MCS0#_108") (pintype "bidirectional"))
      (node (ref "U2") (pin "22") (pinfunction "BS0_22") (pintype "passive"))
    )
    (net (code "38") (name "/MCS1#") (class "Default")
      (node (ref "U1") (pin "109") (pinfunction "MCS1#_109") (pintype "bidirectional"))
      (node (ref "U2") (pin "23") (pinfunction "BS1_23") (pintype "passive"))
    )
    (net (code "39") (name "/MD0") (class "Default")
      (node (ref "U1") (pin "78") (pinfunction "MD0_78") (pintype "bidirectional"))
      (node (ref "U2") (pin "2") (pinfunction "DQ0_2") (pintype "bidirectional"))
    )
    (net (code "40") (name "/MD1") (class "Default")
      (node (ref "U1") (pin "80") (pinfunction "MD1_80") (pintype "bidirectional"))
      (node (ref "U2") (pin "4") (pinfunction "DQ1_4") (pintype "bidirectional"))
    )
    (net (code "41") (name "/MD2") (class "Default")
      (node (ref "U1") (pin "84") (pinfunction "MD2_84") (pintype "bidirectional"))
      (node (ref "U2") (pin "5") (pinfunction "DQ2_5") (pintype "bidirectional"))
    )
    (net (code "42") (name "/MD3") (class "Default")
      (node (ref "U1") (pin "86") (pinfunction "MD3_86") (pintype "bidirectional"))
      (node (ref "U2") (pin "7") (pinfunction "DQ3_7") (pintype "bidirectional"))
    )
    (net (code "43") (name "/MD4") (class "Default")
      (node (ref "U1") (pin "88") (pinfunction "MD4_88") (pintype "bidirectional"))
      (node (ref "U2") (pin "8") (pinfunction "DQ4_8") (pintype "bidirectional"))
    )
    (net (code "44") (name "/MD5") (class "Default")
      (node (ref "U1") (pin "90") (pinfunction "MD5_90") (pintype "bidirectional"))
      (node (ref "U2") (pin "10") (pinfunction "DQ5_10") (pintype "bidirectional"))
    )
    (net (code "45") (name "/MD6") (class "Default")
      (node (ref "U1") (pin "91") (pinfunction "MD6_91") (pintype "bidirectional"))
      (node (ref "U2") (pin "11") (pinfunction "DQ6_11") (pintype "bidirectional"))
    )
    (net (code "46") (name "/MD7") (class "Default")
      (node (ref "U1") (pin "96") (pinfunction "MD7_96") (pintype "bidirectional"))
      (node (ref "U2") (pin "13") (pinfunction "DQ7_13") (pintype "bidirectional"))
    )
    (net (code "47") (name "/MD8") (class "Default")
      (node (ref "U1") (pin "97") (pinfunction "MD8_97") (pintype "bidirectional"))
      (node (ref "U2") (pin "74") (pinfunction "DQ8_74") (pintype "bidirectional"))
    )
    (net (code "48") (name "/MD9") (class "Default")
      (node (ref "U1") (pin "94") (pinfunction "MD9_94") (pintype "bidirectional"))
      (node (ref "U2") (pin "76") (pinfunction "DQ9_76") (pintype "bidirectional"))
    )
    (net (code "49") (name "/MD10") (class "Default")
      (node (ref "U1") (pin "95") (pinfunction "MD10_95") (pintype "bidirectional"))
      (node (ref "U2") (pin "77") (pinfunction "DQ10_77") (pintype "bidirectional"))
    )
    (net (code "50") (name "/MD11") (class "Default")
      (node (ref "U1") (pin "89") (pinfunction "MD11_89") (pintype "bidirectional"))
      (node (ref "U2") (pin "79") (pinfunction "DQ11_79") (pintype "bidirectional"))
    )
    (net (code "51") (name "/MD12") (class "Default")
      (node (ref "U1") (pin "87") (pinfunction "MD12_87") (pintype "bidirectional"))
      (node (ref "U2") (pin "80") (pinfunction "DQ12_80") (pintype "bidirectional"))
    )
    (net (code "52") (name "/MD13") (class "Default")
      (node (ref "U1") (pin "85") (pinfunction "MD13_85") (pintype "bidirectional"))
      (node (ref "U2") (pin "82") (pinfunction "DQ13_82") (pintype "bidirectional"))
    )
    (net (code "53") (name "/MD14") (class "Default")
      (node (ref "U1") (pin "81") (pinfunction "MD14_81") (pintype "bidirectional"))
      (node (ref "U2") (pin "83") (pinfunction "DQ14_83") (pintype "bidirectional"))
    )
    (net (code "54") (name "/MD15") (class "Default")
      (node (ref "U1") (pin "79") (pinfunction "MD15_79") (pintype "bidirectional"))
      (node (ref "U2") (pin "85") (pinfunction "DQ15_85") (pintype "bidirectional"))
    )
    (net (code "55") (name "/MD16") (class "Default")
      (node (ref "U1") (pin "131") (pinfunction "MD16_131") (pintype "bidirectional"))
      (node (ref "U2") (pin "31") (pinfunction "DQ16_31") (pintype "bidirectional"))
    )
    (net (code "56") (name "/MD17") (class "Default")
      (node (ref "U1") (pin "133") (pinfunction "MD17_133") (pintype "bidirectional"))
      (node (ref "U2") (pin "33") (pinfunction "DQ17_33") (pintype "bidirectional"))
    )
    (net (code "57") (name "/MD18") (class "Default")
      (node (ref "U1") (pin "137") (pinfunction "MD18_137") (pintype "bidirectional"))
      (node (ref "U2") (pin "34") (pinfunction "DQ18_34") (pintype "bidirectional"))
    )
    (net (code "58") (name "/MD19") (class "Default")
      (node (ref "U1") (pin "139") (pinfunction "MD19_139") (pintype "bidirectional"))
      (node (ref "U2") (pin "36") (pinfunction "DQ19_36") (pintype "bidirectional"))
    )
    (net (code "59") (name "/MD20") (class "Default")
      (node (ref "U1") (pin "141") (pinfunction "MD20_141") (pintype "bidirectional"))
      (node (ref "U2") (pin "37") (pinfunction "DQ20_37") (pintype "bidirectional"))
    )
    (net (code "60") (name "/MD21") (class "Default")
      (node (ref "U1") (pin "145") (pinfunction "MD21_145") (pintype "bidirectional"))
      (node (ref "U2") (pin "39") (pinfunction "DQ21_39") (pintype "bidirectional"))
    )
    (net (code "61") (name "/MD22") (class "Default")
      (node (ref "U1") (pin "149") (pinfunction "MD22_149") (pintype "bidirectional"))
      (node (ref "U2") (pin "40") (pinfunction "DQ22_40") (pintype "bidirectional"))
    )
    (net (code "62") (name "/MD23") (class "Default")
      (node (ref "U1") (pin "151") (pinfunction "MD23_151") (pintype "bidirectional"))
      (node (ref "U2") (pin "42") (pinfunction "DQ23_42") (pintype "bidirectional"))
    )
    (net (code "63") (name "/MD24") (class "Default")
      (node (ref "U1") (pin "152") (pinfunction "MD24_152") (pintype "bidirectional"))
      (node (ref "U2") (pin "45") (pinfunction "DQ24_45") (pintype "bidirectional"))
    )
    (net (code "64") (name "/MD25") (class "Default")
      (node (ref "U1") (pin "150") (pinfunction "MD25_150") (pintype "bidirectional"))
      (node (ref "U2") (pin "47") (pinfunction "DQ25_47") (pintype "bidirectional"))
    )
    (net (code "65") (name "/MD26") (class "Default")
      (node (ref "U1") (pin "146") (pinfunction "MD26_146") (pintype "bidirectional"))
      (node (ref "U2") (pin "48") (pinfunction "DQ26_48") (pintype "bidirectional"))
    )
    (net (code "66") (name "/MD27") (class "Default")
      (node (ref "U1") (pin "144") (pinfunction "MD27_144") (pintype "bidirectional"))
      (node (ref "U2") (pin "50") (pinfunction "DQ27_50") (pintype "bidirectional"))
    )
    (net (code "67") (name "/MD28") (class "Default")
      (node (ref "U1") (pin "140") (pinfunction "MD28_140") (pintype "bidirectional"))
      (node (ref "U2") (pin "51") (pinfunction "DQ28_51") (pintype "bidirectional"))
    )
    (net (code "68") (name "/MD29") (class "Default")
      (node (ref "U1") (pin "138") (pinfunction "MD29_138") (pintype "bidirectional"))
      (node (ref "U2") (pin "53") (pinfunction "DQ29_53") (pintype "bidirectional"))
    )
    (net (code "69") (name "/MD30") (class "Default")
      (node (ref "U1") (pin "134") (pinfunction "MD30_134") (pintype "bidirectional"))
      (node (ref "U2") (pin "54") (pinfunction "DQ30_54") (pintype "bidirectional"))
    )
    (net (code "70") (name "/MD31") (class "Default")
      (node (ref "U1") (pin "132") (pinfunction "MD31_132") (pintype "bidirectional"))
      (node (ref "U2") (pin "56") (pinfunction "DQ31_56") (pintype "bidirectional"))
    )
    (net (code "71") (name "/PCLK") (class "Default")
      (node (ref "U1") (pin "40") (pinfunction "PCLKIN_40") (pintype "bidirectional"))
      (node (ref "U5") (pin "10") (pinfunction "CLK0_10") (pintype "output"))
    )
    (net (code "72") (name "/R") (class "Default")
      (node (ref "J2") (pin "1") (pinfunction "1_1") (pintype "passive"))
      (node (ref "R3") (pin "1") (pinfunction "1_1") (pintype "passive"))
      (node (ref "R4") (pin "2") (pinfunction "2_2") (pintype "passive"))
    )
    (net (code "73") (name "/RAS#") (class "Default")
      (node (ref "U1") (pin "106") (pinfunction "RAS#_106") (pintype "bidirectional"))
      (node (ref "U2") (pin "19") (pinfunction "~{RAS}_19") (pintype "input"))
    )
    (net (code "74") (name "/ROUT") (class "Default")
      (node (ref "C56") (pin "1") (pinfunction "1_1") (pintype "passive"))
      (node (ref "L2") (pin "1") (pinfunction "P$1_1") (pintype "bidirectional"))
      (node (ref "R18") (pin "1") (pinfunction "1_1") (pintype "passive"))
      (node (ref "U1") (pin "160") (pinfunction "AGPR_160") (pintype "bidirectional"))
    )
    (net (code "75") (name "/RTS") (class "Default")
      (node (ref "U6") (pin "14") (pinfunction "~{RTS}_14") (pintype "bidirectional"))
    )
    (net (code "76") (name "/R_VGA") (class "Default")
      (node (ref "C56") (pin "2") (pinfunction "2_2") (pintype "passive"))
      (node (ref "C59") (pin "1") (pinfunction "1_1") (pintype "passive"))
      (node (ref "J3") (pin "1") (pinfunction "1_1") (pintype "passive"))
      (node (ref "L2") (pin "2") (pinfunction "P$2_2") (pintype "bidirectional"))
    )
    (net (code "77") (name "/S") (class "Default")
      (node (ref "C6") (pin "2") (pinfunction "2_2") (pintype "passive"))
      (node (ref "J2") (pin "7") (pinfunction "7_7") (pintype "passive"))
      (node (ref "R9") (pin "2") (pinfunction "2_2") (pintype "passive"))
    )
    (net (code "78") (name "/SCL") (class "Default")
      (node (ref "R23") (pin "2") (pinfunction "2_2") (pintype "passive"))
      (node (ref "U1") (pin "41") (pinfunction "SCLCK_41") (pintype "bidirectional"))
      (node (ref "U3") (pin "P$9") (pinfunction "GPIO5_P$9") (pintype "bidirectional"))
      (node (ref "U5") (pin "4") (pinfunction "SCL_4") (pintype "input"))
    )
    (net (code "79") (name "/SDA") (class "Default")
      (node (ref "R22") (pin "2") (pinfunction "2_2") (pintype "passive"))
      (node (ref "U1") (pin "42") (pinfunction "SCLDA_42") (pintype "bidirectional"))
      (node (ref "U3") (pin "P$12") (pinfunction "GPIO4_P$12") (pintype "bidirectional"))
      (node (ref "U5") (pin "5") (pinfunction "SDA_5") (pintype "bidirectional"))
    )
    (net (code "80") (name "/V") (class "Default")
      (node (ref "J3") (pin "9") (pinfunction "9_9") (pintype "passive"))
      (node (ref "R21") (pin "1") (pinfunction "1_1") (pintype "passive"))
    )
    (net (code "81") (name "/VS") (class "Default")
      (node (ref "C62") (pin "1") (pinfunction "1_1") (pintype "passive"))
      (node (ref "R21") (pin "2") (pinfunction "2_2") (pintype "passive"))
      (node (ref "U4") (pin "6") (pinfunction "O_6") (pintype "tri_state"))
    )
    (net (code "82") (name "/VSOUT") (class "Default")
      (node (ref "U1") (pin "2") (pinfunction "VSOUT_2") (pintype "bidirectional"))
      (node (ref "U4") (pin "5") (pinfunction "I_5") (pintype "input"))
    )
    (net (code "83") (name "/WE#") (class "Default")
      (node (ref "U1") (pin "99") (pinfunction "WE#_99") (pintype "bidirectional"))
      (node (ref "U2") (pin "17") (pinfunction "~{WE}_17") (pintype "passive"))
    )
    (net (code "84") (name "1.8V") (class "Default")
      (node (ref "C14") (pin "1") (pinfunction "1_1") (pintype "passive"))
      (node (ref "C15") (pin "1") (pinfunction "1_1") (pintype "passive"))
      (node (ref "C16") (pin "1") (pinfunction "1_1") (pintype "passive"))
      (node (ref "C17") (pin "1") (pinfunction "1_1") (pintype "passive"))
      (node (ref "C18") (pin "1") (pinfunction "1_1") (pintype "passive"))
      (node (ref "C19") (pin "1") (pinfunction "1_1") (pintype "passive"))
      (node (ref "C54") (pin "1") (pinfunction "1_1") (pintype "passive"))
      (node (ref "U1") (pin "102") (pinfunction "VDD2_102") (pintype "bidirectional"))
      (node (ref "U1") (pin "142") (pinfunction "VDD3_142") (pintype "bidirectional"))
      (node (ref "U1") (pin "16") (pinfunction "VDD_16") (pintype "bidirectional"))
      (node (ref "U8") (pin "4") (pinfunction "OUT_4") (pintype "bidirectional"))
    )
    (net (code "85") (name "GND") (class "Default")
      (node (ref "ANT1") (pin "P$1") (pinfunction "GND_P$1") (pintype "input"))
      (node (ref "C1") (pin "2") (pinfunction "2_2") (pintype "passive"))
      (node (ref "C10") (pin "1") (pinfunction "1_1") (pintype "passive"))
      (node (ref "C11") (pin "1") (pinfunction "1_1") (pintype "passive"))
      (node (ref "C12") (pin "2") (pinfunction "2_2") (pintype "passive"))
      (node (ref "C13") (pin "2") (pinfunction "2_2") (pintype "passive"))
      (node (ref "C14") (pin "2") (pinfunction "2_2") (pintype "passive"))
      (node (ref "C15") (pin "2") (pinfunction "2_2") (pintype "passive"))
      (node (ref "C16") (pin "2") (pinfunction "2_2") (pintype "passive"))
      (node (ref "C17") (pin "2") (pinfunction "2_2") (pintype "passive"))
      (node (ref "C18") (pin "2") (pinfunction "2_2") (pintype "passive"))
      (node (ref "C19") (pin "2") (pinfunction "2_2") (pintype "passive"))
      (node (ref "C2") (pin "2") (pinfunction "2_2") (pintype "passive"))
      (node (ref "C20") (pin "2") (pinfunction "2_2") (pintype "passive"))
      (node (ref "C21") (pin "2") (pinfunction "2_2") (pintype "passive"))
      (node (ref "C22") (pin "2") (pinfunction "2_2") (pintype "passive"))
      (node (ref "C23") (pin "2") (pinfunction "2_2") (pintype "passive"))
      (node (ref "C24") (pin "2") (pinfunction "2_2") (pintype "passive"))
      (node (ref "C25") (pin "2") (pinfunction "2_2") (pintype "passive"))
      (node (ref "C26") (pin "2") (pinfunction "2_2") (pintype "passive"))
      (node (ref "C27") (pin "2") (pinfunction "2_2") (pintype "passive"))
      (node (ref "C28") (pin "2") (pinfunction "2_2") (pintype "passive"))
      (node (ref "C29") (pin "2") (pinfunction "2_2") (pintype "passive"))
      (node (ref "C30") (pin "2") (pinfunction "2_2") (pintype "passive"))
      (node (ref "C31") (pin "2") (pinfunction "2_2") (pintype "passive"))
      (node (ref "C32") (pin "2") (pinfunction "2_2") (pintype "passive"))
      (node (ref "C33") (pin "2") (pinfunction "2_2") (pintype "passive"))
      (node (ref "C34") (pin "2") (pinfunction "2_2") (pintype "passive"))
      (node (ref "C35") (pin "2") (pinfunction "2_2") (pintype "passive"))
      (node (ref "C36") (pin "2") (pinfunction "2_2") (pintype "passive"))
      (node (ref "C37") (pin "2") (pinfunction "2_2") (pintype "passive"))
      (node (ref "C38") (pin "2") (pinfunction "2_2") (pintype "passive"))
      (node (ref "C39") (pin "2") (pinfunction "2_2") (pintype "passive"))
      (node (ref "C40") (pin "2") (pinfunction "2_2") (pintype "passive"))
      (node (ref "C41") (pin "2") (pinfunction "2_2") (pintype "passive"))
      (node (ref "C42") (pin "2") (pinfunction "2_2") (pintype "passive"))
      (node (ref "C43") (pin "2") (pinfunction "2_2") (pintype "passive"))
      (node (ref "C44") (pin "2") (pinfunction "2_2") (pintype "passive"))
      (node (ref "C45") (pin "2") (pinfunction "2_2") (pintype "passive"))
      (node (ref "C46") (pin "2") (pinfunction "2_2") (pintype "passive"))
      (node (ref "C47") (pin "2") (pinfunction "2_2") (pintype "passive"))
      (node (ref "C48") (pin "2") (pinfunction "2_2") (pintype "passive"))
      (node (ref "C49") (pin "2") (pinfunction "2_2") (pintype "passive"))
      (node (ref "C50") (pin "2") (pinfunction "2_2") (pintype "passive"))
      (node (ref "C51") (pin "2") (pinfunction "2_2") (pintype "passive"))
      (node (ref "C52") (pin "2") (pinfunction "2_2") (pintype "passive"))
      (node (ref "C53") (pin "2") (pinfunction "2_2") (pintype "passive"))
      (node (ref "C54") (pin "2") (pinfunction "2_2") (pintype "passive"))
      (node (ref "C55") (pin "2") (pinfunction "2_2") (pintype "passive"))
      (node (ref "C59") (pin "2") (pinfunction "2_2") (pintype "passive"))
      (node (ref "C60") (pin "2") (pinfunction "2_2") (pintype "passive"))
      (node (ref "C61") (pin "2") (pinfunction "2_2") (pintype "passive"))
      (node (ref "C62") (pin "2") (pinfunction "2_2") (pintype "passive"))
      (node (ref "C63") (pin "2") (pinfunction "2_2") (pintype "passive"))
      (node (ref "C9") (pin "1") (pinfunction "1_1") (pintype "passive"))
      (node (ref "J1") (pin "1") (pinfunction "GND_1") (pintype "passive"))
      (node (ref "J1") (pin "13") (pinfunction "GND_13") (pintype "passive"))
      (node (ref "J1") (pin "14") (pinfunction "GND_14") (pintype "passive"))
      (node (ref "J1") (pin "15") (pinfunction "GND_15") (pintype "passive"))
      (node (ref "J1") (pin "16") (pinfunction "GND_16") (pintype "passive"))
      (node (ref "J1") (pin "2") (pinfunction "GND_2") (pintype "passive"))
      (node (ref "J1") (pin "3") (pinfunction "GND_3") (pintype "passive"))
      (node (ref "J1") (pin "4") (pinfunction "GND_4") (pintype "passive"))
      (node (ref "J1") (pin "A1/B12") (pinfunction "GND_2_A1/B12") (pintype "passive"))
      (node (ref "J1") (pin "B1/A12") (pinfunction "GND_B1/A12") (pintype "passive"))
      (node (ref "J1") (pin "S_1_H1") (pinfunction "GND_S_1_H1") (pintype "passive"))
      (node (ref "J1") (pin "S_1_H2") (pinfunction "GND_S_1_H2") (pintype "passive"))
      (node (ref "J1") (pin "S_2_H1") (pinfunction "GND_S_2_H1") (pintype "passive"))
      (node (ref "J1") (pin "S_2_H2") (pinfunction "GND_S_2_H2") (pintype "passive"))
      (node (ref "J1") (pin "S_3_H1") (pinfunction "GND_S_3_H1") (pintype "passive"))
      (node (ref "J1") (pin "S_3_H2") (pinfunction "GND_S_3_H2") (pintype "passive"))
      (node (ref "J1") (pin "S_4_H1") (pinfunction "GND_S_4_H1") (pintype "passive"))
      (node (ref "J1") (pin "S_4_H2") (pinfunction "GND_S_4_H2") (pintype "passive"))
      (node (ref "J2") (pin "2") (pinfunction "2_2") (pintype "passive"))
      (node (ref "J2") (pin "4") (pinfunction "4_4") (pintype "passive"))
      (node (ref "J2") (pin "6") (pinfunction "6_6") (pintype "passive"))
      (node (ref "J3") (pin "10") (pinfunction "10_10") (pintype "passive"))
      (node (ref "J3") (pin "2") (pinfunction "2_2") (pintype "passive"))
      (node (ref "J3") (pin "4") (pinfunction "4_4") (pintype "passive"))
      (node (ref "J3") (pin "6") (pinfunction "6_6") (pintype "passive"))
      (node (ref "J3") (pin "8") (pinfunction "8_8") (pintype "passive"))
      (node (ref "J4") (pin "2") (pinfunction "2_2") (pintype "passive"))
      (node (ref "J5") (pin "2") (pinfunction "2_2") (pintype "passive"))
      (node (ref "R12") (pin "2") (pinfunction "2_2") (pintype "passive"))
      (node (ref "R13") (pin "2") (pinfunction "2_2") (pintype "passive"))
      (node (ref "R14") (pin "1") (pinfunction "1_1") (pintype "passive"))
      (node (ref "R16") (pin "2") (pinfunction "2_2") (pintype "passive"))
      (node (ref "R17") (pin "2") (pinfunction "2_2") (pintype "passive"))
      (node (ref "R18") (pin "2") (pinfunction "2_2") (pintype "passive"))
      (node (ref "R2") (pin "2") (pinfunction "2_2") (pintype "passive"))
      (node (ref "R28") (pin "2") (pinfunction "2_2") (pintype "passive"))
      (node (ref "R4") (pin "1") (pinfunction "1_1") (pintype "passive"))
      (node (ref "R6") (pin "1") (pinfunction "1_1") (pintype "passive"))
      (node (ref "R8") (pin "1") (pinfunction "1_1") (pintype "passive"))
      (node (ref "R9") (pin "1") (pinfunction "1_1") (pintype "passive"))
      (node (ref "U1") (pin "101") (pinfunction "VSS2_101") (pintype "bidirectional"))
      (node (ref "U1") (pin "105") (pinfunction "PVSS7_105") (pintype "bidirectional"))
      (node (ref "U1") (pin "113") (pinfunction "PVSS8_113") (pintype "bidirectional"))
      (node (ref "U1") (pin "122") (pinfunction "PAVS_122") (pintype "bidirectional"))
      (node (ref "U1") (pin "126") (pinfunction "PVSS9_126") (pintype "bidirectional"))
      (node (ref "U1") (pin "13") (pinfunction "PVSS2_13") (pintype "bidirectional"))
      (node (ref "U1") (pin "136") (pinfunction "PVSS10_136") (pintype "bidirectional"))
      (node (ref "U1") (pin "143") (pinfunction "VSS3_143") (pintype "bidirectional"))
      (node (ref "U1") (pin "148") (pinfunction "PVSS11_148") (pintype "bidirectional"))
      (node (ref "U1") (pin "153") (pinfunction "DVSS_153") (pintype "bidirectional"))
      (node (ref "U1") (pin "156") (pinfunction "DAVS_156") (pintype "bidirectional"))
      (node (ref "U1") (pin "17") (pinfunction "VSS_17") (pintype "bidirectional"))
      (node (ref "U1") (pin "25") (pinfunction "PVSS3_25") (pintype "bidirectional"))
      (node (ref "U1") (pin "35") (pinfunction "PVSS4_35") (pintype "bidirectional"))
      (node (ref "U1") (pin "43") (pinfunction "SCLSA_43") (pintype "bidirectional"))
      (node (ref "U1") (pin "5") (pinfunction "PVSS_5") (pintype "bidirectional"))
      (node (ref "U1") (pin "50") (pinfunction "AVS_PLL_50") (pintype "bidirectional"))
      (node (ref "U1") (pin "53") (pinfunction "AVS_REF_53") (pintype "bidirectional"))
      (node (ref "U1") (pin "56") (pinfunction "AVS_R_56") (pintype "bidirectional"))
      (node (ref "U1") (pin "58") (pinfunction "AVS_R2_58") (pintype "bidirectional"))
      (node (ref "U1") (pin "63") (pinfunction "AVS_G_63") (pintype "bidirectional"))
      (node (ref "U1") (pin "66") (pinfunction "AVS_G2_66") (pintype "bidirectional"))
      (node (ref "U1") (pin "70") (pinfunction "AVS_B_70") (pintype "bidirectional"))
      (node (ref "U1") (pin "72") (pinfunction "AVS_B2_72") (pintype "bidirectional"))
      (node (ref "U1") (pin "74") (pinfunction "AVS_B3_74") (pintype "bidirectional"))
      (node (ref "U1") (pin "83") (pinfunction "PVSS5_83") (pintype "bidirectional"))
      (node (ref "U1") (pin "93") (pinfunction "PVSS6_93") (pintype "bidirectional"))
      (node (ref "U2") (pin "12") (pinfunction "VSSQ_3_12") (pintype "power_in"))
      (node (ref "U2") (pin "20") (pinfunction "~{CS}_20") (pintype "passive"))
      (node (ref "U2") (pin "32") (pinfunction "VSSQ_4_32") (pintype "power_in"))
      (node (ref "U2") (pin "38") (pinfunction "VSSQ_5_38") (pintype "power_in"))
      (node (ref "U2") (pin "44") (pinfunction "VSS_2_44") (pintype "power_in"))
      (node (ref "U2") (pin "46") (pinfunction "VSSQ_6_46") (pintype "power_in"))
      (node (ref "U2") (pin "52") (pinfunction "VSSQ_7_52") (pintype "power_in"))
      (node (ref "U2") (pin "58") (pinfunction "VSS_3_58") (pintype "power_in"))
      (node (ref "U2") (pin "6") (pinfunction "VSSQ_2_6") (pintype "power_in"))
      (node (ref "U2") (pin "72") (pinfunction "VSS_4_72") (pintype "power_in"))
      (node (ref "U2") (pin "78") (pinfunction "VSSQ_8_78") (pintype "power_in"))
      (node (ref "U2") (pin "84") (pinfunction "VSSQ_84") (pintype "power_in"))
      (node (ref "U2") (pin "86") (pinfunction "VSS_86") (pintype "power_in"))
      (node (ref "U3") (pin "P$17") (pinfunction "GND_P$17") (pintype "bidirectional"))
      (node (ref "U3") (pin "P$18") (pinfunction "GND_P$18") (pintype "bidirectional"))
      (node (ref "U3") (pin "P$19") (pinfunction "GND_P$19") (pintype "bidirectional"))
      (node (ref "U3") (pin "P$20") (pinfunction "GND_P$20") (pintype "bidirectional"))
      (node (ref "U3") (pin "P$5") (pinfunction "GND_P$5") (pintype "bidirectional"))
      (node (ref "U4") (pin "1") (pinfunction "OE_1") (pintype "input"))
      (node (ref "U4") (pin "4") (pinfunction "OE_4") (pintype "input"))
      (node (ref "U4") (pin "7") (pinfunction "GND_7") (pintype "power_in"))
      (node (ref "U5") (pin "8") (pinfunction "GND_8") (pintype "power_in"))
      (node (ref "U6") (pin "1") (pinfunction "GND_1") (pintype "bidirectional"))
      (node (ref "U7") (pin "10") (pinfunction "MODE_10") (pintype "input"))
      (node (ref "U7") (pin "11") (pinfunction "VSEL_11") (pintype "input"))
      (node (ref "U7") (pin "3") (pinfunction "GND_3") (pintype "power_in"))
      (node (ref "U7") (pin "4") (pinfunction "FB2_4") (pintype "open_collector"))
      (node (ref "U7") (pin "7") (pinfunction "PG_7") (pintype "open_collector"))
      (node (ref "U8") (pin "2") (pinfunction "GND_2") (pintype "bidirectional"))
      (node (ref "U8") (pin "7") (pinfunction "EP_7") (pintype "bidirectional"))
    )
    (net (code "86") (name "Net-(ANT1-ANT)") (class "Default")
      (node (ref "ANT1") (pin "P$2") (pinfunction "ANT_P$2") (pintype "input"))
      (node (ref "U3") (pin "P$4") (pinfunction "ANT_P$4") (pintype "bidirectional"))
    )
    (net (code "87") (name "Net-(C3-Pad1)") (class "Default")
      (node (ref "C3") (pin "1") (pinfunction "1_1") (pintype "passive"))
      (node (ref "R3") (pin "2") (pinfunction "2_2") (pintype "passive"))
    )
    (net (code "88") (name "Net-(C4-Pad1)") (class "Default")
      (node (ref "C4") (pin "1") (pinfunction "1_1") (pintype "passive"))
      (node (ref "R5") (pin "2") (pinfunction "2_2") (pintype "passive"))
    )
    (net (code "89") (name "Net-(C5-Pad1)") (class "Default")
      (node (ref "C5") (pin "1") (pinfunction "1_1") (pintype "passive"))
      (node (ref "R7") (pin "2") (pinfunction "2_2") (pintype "passive"))
    )
    (net (code "90") (name "Net-(C7-Pad1)") (class "Default")
      (node (ref "C7") (pin "1") (pinfunction "1_1") (pintype "passive"))
      (node (ref "R10") (pin "1") (pinfunction "1_1") (pintype "passive"))
    )
    (net (code "91") (name "Net-(J1-CC1)") (class "Default")
      (node (ref "J1") (pin "A5") (pinfunction "CC1_A5") (pintype "bidirectional"))
      (node (ref "R12") (pin "1") (pinfunction "1_1") (pintype "passive"))
    )
    (net (code "92") (name "Net-(J1-CC2)") (class "Default")
      (node (ref "J1") (pin "B5") (pinfunction "CC2_B5") (pintype "bidirectional"))
      (node (ref "R13") (pin "1") (pinfunction "1_1") (pintype "passive"))
    )
    (net (code "93") (name "Net-(LED1-PadA)") (class "Default")
      (node (ref "LED1") (pin "A") (pinfunction "A_A") (pintype "passive"))
      (node (ref "R24") (pin "2") (pinfunction "2_2") (pintype "passive"))
    )
    (net (code "94") (name "Net-(LED2-PadA)") (class "Default")
      (node (ref "LED2") (pin "A") (pinfunction "A_A") (pintype "passive"))
      (node (ref "R25") (pin "2") (pinfunction "2_2") (pintype "passive"))
    )
    (net (code "95") (name "Net-(U1-B1)") (class "Default")
      (node (ref "C5") (pin "2") (pinfunction "2_2") (pintype "passive"))
      (node (ref "U1") (pin "71") (pinfunction "B1_71") (pintype "bidirectional"))
    )
    (net (code "96") (name "Net-(U1-FILT)") (class "Default")
      (node (ref "C8") (pin "1") (pinfunction "1_1") (pintype "passive"))
      (node (ref "R10") (pin "2") (pinfunction "2_2") (pintype "passive"))
      (node (ref "U1") (pin "49") (pinfunction "FILT_49") (pintype "bidirectional"))
    )
    (net (code "97") (name "Net-(U1-G1)") (class "Default")
      (node (ref "C4") (pin "2") (pinfunction "2_2") (pintype "passive"))
      (node (ref "U1") (pin "65") (pinfunction "G1_65") (pintype "bidirectional"))
    )
    (net (code "98") (name "Net-(U1-IREF)") (class "Default")
      (node (ref "R2") (pin "1") (pinfunction "1_1") (pintype "passive"))
      (node (ref "U1") (pin "155") (pinfunction "IREF_155") (pintype "bidirectional"))
    )
    (net (code "99") (name "Net-(U1-R1)") (class "Default")
      (node (ref "C3") (pin "2") (pinfunction "2_2") (pintype "passive"))
      (node (ref "U1") (pin "57") (pinfunction "R1_57") (pintype "bidirectional"))
    )
    (net (code "100") (name "Net-(U1-REFBP)") (class "Default")
      (node (ref "C9") (pin "2") (pinfunction "2_2") (pintype "passive"))
      (node (ref "U1") (pin "52") (pinfunction "REFBP_52") (pintype "bidirectional"))
    )
    (net (code "101") (name "Net-(U1-RSTN)") (class "Default")
      (node (ref "R1") (pin "2") (pinfunction "2_2") (pintype "passive"))
      (node (ref "U1") (pin "75") (pinfunction "RSTN_75") (pintype "bidirectional"))
    )
    (net (code "102") (name "Net-(U1-SOG1)") (class "Default")
      (node (ref "C6") (pin "1") (pinfunction "1_1") (pintype "passive"))
      (node (ref "U1") (pin "64") (pinfunction "SOG1_64") (pintype "bidirectional"))
    )
    (net (code "103") (name "Net-(U1-XTIN)") (class "Default")
      (node (ref "C11") (pin "2") (pinfunction "2_2") (pintype "passive"))
      (node (ref "R11") (pin "2") (pinfunction "2_2") (pintype "passive"))
      (node (ref "U1") (pin "124") (pinfunction "XTIN_124") (pintype "bidirectional"))
      (node (ref "Y1") (pin "3") (pinfunction "2_3") (pintype "passive"))
    )
    (net (code "104") (name "Net-(U1-XTOUT)") (class "Default")
      (node (ref "C10") (pin "2") (pinfunction "2_2") (pintype "passive"))
      (node (ref "R11") (pin "1") (pinfunction "1_1") (pintype "passive"))
      (node (ref "U1") (pin "125") (pinfunction "XTOUT_125") (pintype "bidirectional"))
      (node (ref "Y1") (pin "1") (pinfunction "1_1") (pintype "passive"))
    )
    (net (code "105") (name "Net-(U5-XA)") (class "Default")
      (node (ref "U5") (pin "2") (pinfunction "XA_2") (pintype "input"))
      (node (ref "Y2") (pin "3") (pinfunction "2_3") (pintype "passive"))
    )
    (net (code "106") (name "Net-(U5-XB)") (class "Default")
      (node (ref "U5") (pin "3") (pinfunction "XB_3") (pintype "input"))
      (node (ref "Y2") (pin "1") (pinfunction "1_1") (pintype "passive"))
    )
    (net (code "107") (name "Net-(U7-FB)") (class "Default")
      (node (ref "R14") (pin "2") (pinfunction "2_2") (pintype "passive"))
      (node (ref "R15") (pin "1") (pinfunction "1_1") (pintype "passive"))
      (node (ref "U7") (pin "5") (pinfunction "FB_5") (pintype "input"))
    )
    (net (code "108") (name "Net-(U7-SW)") (class "Default")
      (node (ref "L1") (pin "1") (pinfunction "1_1") (pintype "bidirectional"))
      (node (ref "U7") (pin "2") (pinfunction "SW_2") (pintype "power_in"))
    )
    (net (code "109") (name "Net-(U7-VOS)") (class "Default")
      (node (ref "C35") (pin "1") (pinfunction "1_1") (pintype "passive"))
      (node (ref "C36") (pin "1") (pinfunction "1_1") (pintype "passive"))
      (node (ref "L1") (pin "2") (pinfunction "2_2") (pintype "bidirectional"))
      (node (ref "R15") (pin "2") (pinfunction "2_2") (pintype "passive"))
      (node (ref "R19") (pin "1") (pinfunction "1_1") (pintype "passive"))
      (node (ref "U7") (pin "6") (pinfunction "VOS_6") (pintype "input"))
    )
    (net (code "110") (name "unconnected-(J1-SBU1-PadA8)") (class "Default")
      (node (ref "J1") (pin "A8") (pinfunction "SBU1_A8") (pintype "bidirectional"))
    )
    (net (code "111") (name "unconnected-(J1-SBU2-PadB8)") (class "Default")
      (node (ref "J1") (pin "B8") (pinfunction "SBU2_B8") (pintype "bidirectional"))
    )
    (net (code "112") (name "unconnected-(U1-ASVM-Pad154)") (class "Default")
      (node (ref "U1") (pin "154") (pinfunction "ASVM_154") (pintype "bidirectional"))
    )
    (net (code "113") (name "unconnected-(U1-B0-Pad69)") (class "Default")
      (node (ref "U1") (pin "69") (pinfunction "B0_69") (pintype "bidirectional"))
    )
    (net (code "114") (name "unconnected-(U1-B2-Pad73)") (class "Default")
      (node (ref "U1") (pin "73") (pinfunction "B2_73") (pintype "bidirectional"))
    )
    (net (code "115") (name "unconnected-(U1-CLKOUT-Pad4)") (class "Default")
      (node (ref "U1") (pin "4") (pinfunction "CLKOUT_4") (pintype "bidirectional"))
    )
    (net (code "116") (name "unconnected-(U1-G0-Pad62)") (class "Default")
      (node (ref "U1") (pin "62") (pinfunction "G0_62") (pintype "bidirectional"))
    )
    (net (code "117") (name "unconnected-(U1-G2-Pad67)") (class "Default")
      (node (ref "U1") (pin "67") (pinfunction "G2_67") (pintype "bidirectional"))
    )
    (net (code "118") (name "unconnected-(U1-GPIO-Pad76)") (class "Default")
      (node (ref "U1") (pin "76") (pinfunction "GPIO_76") (pintype "bidirectional"))
    )
    (net (code "119") (name "unconnected-(U1-HALF-Pad77)") (class "Default")
      (node (ref "U1") (pin "77") (pinfunction "HALF_77") (pintype "bidirectional"))
    )
    (net (code "120") (name "unconnected-(U1-HBOUT-Pad6)") (class "Default")
      (node (ref "U1") (pin "6") (pinfunction "HBOUT_6") (pintype "bidirectional"))
    )
    (net (code "121") (name "unconnected-(U1-HSIN1-Pad44)") (class "Default")
      (node (ref "U1") (pin "44") (pinfunction "HSIN1_44") (pintype "bidirectional"))
    )
    (net (code "122") (name "unconnected-(U1-HSIN2-Pad46)") (class "Default")
      (node (ref "U1") (pin "46") (pinfunction "HSIN2_46") (pintype "bidirectional"))
    )
    (net (code "123") (name "unconnected-(U1-R0-Pad55)") (class "Default")
      (node (ref "U1") (pin "55") (pinfunction "R0_55") (pintype "bidirectional"))
    )
    (net (code "124") (name "unconnected-(U1-R2-Pad59)") (class "Default")
      (node (ref "U1") (pin "59") (pinfunction "R2_59") (pintype "bidirectional"))
    )
    (net (code "125") (name "unconnected-(U1-SOG0-Pad61)") (class "Default")
      (node (ref "U1") (pin "61") (pinfunction "SOG0_61") (pintype "bidirectional"))
    )
    (net (code "126") (name "unconnected-(U1-VB0-Pad8)") (class "Default")
      (node (ref "U1") (pin "8") (pinfunction "VB0_8") (pintype "bidirectional"))
    )
    (net (code "127") (name "unconnected-(U1-VB1-Pad9)") (class "Default")
      (node (ref "U1") (pin "9") (pinfunction "VB1_9") (pintype "bidirectional"))
    )
    (net (code "128") (name "unconnected-(U1-VB2-Pad10)") (class "Default")
      (node (ref "U1") (pin "10") (pinfunction "VB2_10") (pintype "bidirectional"))
    )
    (net (code "129") (name "unconnected-(U1-VB4-Pad14)") (class "Default")
      (node (ref "U1") (pin "14") (pinfunction "VB4_14") (pintype "bidirectional"))
    )
    (net (code "130") (name "unconnected-(U1-VB5-Pad15)") (class "Default")
      (node (ref "U1") (pin "15") (pinfunction "VB5_15") (pintype "bidirectional"))
    )
    (net (code "131") (name "unconnected-(U1-VB6-Pad18)") (class "Default")
      (node (ref "U1") (pin "18") (pinfunction "VB6_18") (pintype "bidirectional"))
    )
    (net (code "132") (name "unconnected-(U1-VB7-Pad19)") (class "Default")
      (node (ref "U1") (pin "19") (pinfunction "VB7_19") (pintype "bidirectional"))
    )
    (net (code "133") (name "unconnected-(U1-VBOUT-Pad7)") (class "Default")
      (node (ref "U1") (pin "7") (pinfunction "VBOUT_7") (pintype "bidirectional"))
    )
    (net (code "134") (name "unconnected-(U1-VG0-Pad20)") (class "Default")
      (node (ref "U1") (pin "20") (pinfunction "VG0_20") (pintype "bidirectional"))
    )
    (net (code "135") (name "unconnected-(U1-VG1-Pad21)") (class "Default")
      (node (ref "U1") (pin "21") (pinfunction "VG1_21") (pintype "bidirectional"))
    )
    (net (code "136") (name "unconnected-(U1-VG2-Pad22)") (class "Default")
      (node (ref "U1") (pin "22") (pinfunction "VG2_22") (pintype "bidirectional"))
    )
    (net (code "137") (name "unconnected-(U1-VG3-Pad23)") (class "Default")
      (node (ref "U1") (pin "23") (pinfunction "VG3_23") (pintype "bidirectional"))
    )
    (net (code "138") (name "unconnected-(U1-VG4-Pad26)") (class "Default")
      (node (ref "U1") (pin "26") (pinfunction "VG4_26") (pintype "bidirectional"))
    )
    (net (code "139") (name "unconnected-(U1-VG5-Pad27)") (class "Default")
      (node (ref "U1") (pin "27") (pinfunction "VG5_27") (pintype "bidirectional"))
    )
    (net (code "140") (name "unconnected-(U1-VG6-Pad28)") (class "Default")
      (node (ref "U1") (pin "28") (pinfunction "VG6_28") (pintype "bidirectional"))
    )
    (net (code "141") (name "unconnected-(U1-VG7-Pad29)") (class "Default")
      (node (ref "U1") (pin "29") (pinfunction "VG7_29") (pintype "bidirectional"))
    )
    (net (code "142") (name "unconnected-(U1-VR0-Pad30)") (class "Default")
      (node (ref "U1") (pin "30") (pinfunction "VR0_30") (pintype "bidirectional"))
    )
    (net (code "143") (name "unconnected-(U1-VR1-Pad31)") (class "Default")
      (node (ref "U1") (pin "31") (pinfunction "VR1_31") (pintype "bidirectional"))
    )
    (net (code "144") (name "unconnected-(U1-VR2-Pad32)") (class "Default")
      (node (ref "U1") (pin "32") (pinfunction "VR2_32") (pintype "bidirectional"))
    )
    (net (code "145") (name "unconnected-(U1-VR3-Pad33)") (class "Default")
      (node (ref "U1") (pin "33") (pinfunction "VR3_33") (pintype "bidirectional"))
    )
    (net (code "146") (name "unconnected-(U1-VR4-Pad36)") (class "Default")
      (node (ref "U1") (pin "36") (pinfunction "VR4_36") (pintype "bidirectional"))
    )
    (net (code "147") (name "unconnected-(U1-VR5-Pad37)") (class "Default")
      (node (ref "U1") (pin "37") (pinfunction "VR5_37") (pintype "bidirectional"))
    )
    (net (code "148") (name "unconnected-(U1-VR6-Pad38)") (class "Default")
      (node (ref "U1") (pin "38") (pinfunction "VR6_38") (pintype "bidirectional"))
    )
    (net (code "149") (name "unconnected-(U1-VR7-Pad39)") (class "Default")
      (node (ref "U1") (pin "39") (pinfunction "VR7_39") (pintype "bidirectional"))
    )
    (net (code "150") (name "unconnected-(U1-VSIN1-Pad45)") (class "Default")
      (node (ref "U1") (pin "45") (pinfunction "VSIN1_45") (pintype "bidirectional"))
    )
    (net (code "151") (name "unconnected-(U1-VSIN2-Pad47)") (class "Default")
      (node (ref "U1") (pin "47") (pinfunction "VSIN2_47") (pintype "bidirectional"))
    )
    (net (code "152") (name "unconnected-(U2-NC-Pad73)") (class "Default")
      (node (ref "U2") (pin "73") (pinfunction "NC_73") (pintype "no_connect"))
    )
    (net (code "153") (name "unconnected-(U2-NC_2-Pad14)") (class "Default")
      (node (ref "U2") (pin "14") (pinfunction "NC_2_14") (pintype "no_connect"))
    )
    (net (code "154") (name "unconnected-(U2-NC_3-Pad21)") (class "Default")
      (node (ref "U2") (pin "21") (pinfunction "NC_3_21") (pintype "no_connect"))
    )
    (net (code "155") (name "unconnected-(U2-NC_4-Pad30)") (class "Default")
      (node (ref "U2") (pin "30") (pinfunction "NC_4_30") (pintype "no_connect"))
    )
    (net (code "156") (name "unconnected-(U2-NC_5-Pad57)") (class "Default")
      (node (ref "U2") (pin "57") (pinfunction "NC_5_57") (pintype "no_connect"))
    )
    (net (code "157") (name "unconnected-(U2-NC_6-Pad69)") (class "Default")
      (node (ref "U2") (pin "69") (pinfunction "NC_6_69") (pintype "no_connect"))
    )
    (net (code "158") (name "unconnected-(U2-NC_7-Pad70)") (class "Default")
      (node (ref "U2") (pin "70") (pinfunction "NC_7_70") (pintype "no_connect"))
    )
    (net (code "159") (name "unconnected-(U3-GPIO13-PadP$14)") (class "Default")
      (node (ref "U3") (pin "P$14") (pinfunction "GPIO13_P$14") (pintype "bidirectional"))
    )
    (net (code "160") (name "unconnected-(U3-GPIO14-PadP$16)") (class "Default")
      (node (ref "U3") (pin "P$16") (pinfunction "GPIO14_P$16") (pintype "bidirectional"))
    )
    (net (code "161") (name "unconnected-(U3-GPIO16-PadP$1)") (class "Default")
      (node (ref "U3") (pin "P$1") (pinfunction "GPIO16_P$1") (pintype "bidirectional"))
    )
    (net (code "162") (name "unconnected-(U5-CLK1-Pad9)") (class "Default")
      (node (ref "U5") (pin "9") (pinfunction "CLK1_9") (pintype "output"))
    )
    (net (code "163") (name "unconnected-(U5-CLK2-Pad6)") (class "Default")
      (node (ref "U5") (pin "6") (pinfunction "CLK2_6") (pintype "output"))
    )
    (net (code "164") (name "unconnected-(U6-R232-Pad15)") (class "Default")
      (node (ref "U6") (pin "15") (pinfunction "R232_15") (pintype "bidirectional"))
    )
    (net (code "165") (name "unconnected-(U6-~{CTS}-Pad9)") (class "Default")
      (node (ref "U6") (pin "9") (pinfunction "~{CTS}_9") (pintype "bidirectional"))
    )
    (net (code "166") (name "unconnected-(U6-~{DCD}-Pad12)") (class "Default")
      (node (ref "U6") (pin "12") (pinfunction "~{DCD}_12") (pintype "bidirectional"))
    )
    (net (code "167") (name "unconnected-(U6-~{DSR}-Pad10)") (class "Default")
      (node (ref "U6") (pin "10") (pinfunction "~{DSR}_10") (pintype "bidirectional"))
    )
    (net (code "168") (name "unconnected-(U6-~{RI}-Pad11)") (class "Default")
      (node (ref "U6") (pin "11") (pinfunction "~{RI}_11") (pintype "bidirectional"))
    )
    (net (code "169") (name "unconnected-(U7-SS_TR-Pad9)") (class "Default")
      (node (ref "U7") (pin "9") (pinfunction "SS_TR_9") (pintype "input"))
    )
    (net (code "170") (name "unconnected-(U8-NC-Pad5)") (class "Default")
      (node (ref "U8") (pin "5") (pinfunction "NC_5") (pintype "no_connect"))
    )
    (net (code "171") (name "unconnected-(U8-PG-Pad3)") (class "Default")
      (node (ref "U8") (pin "3") (pinfunction "PG_3") (pintype "bidirectional"))
    )
  )
)
